# AFE.net
KiCad netlist of a schematic drawn in Altium Designer
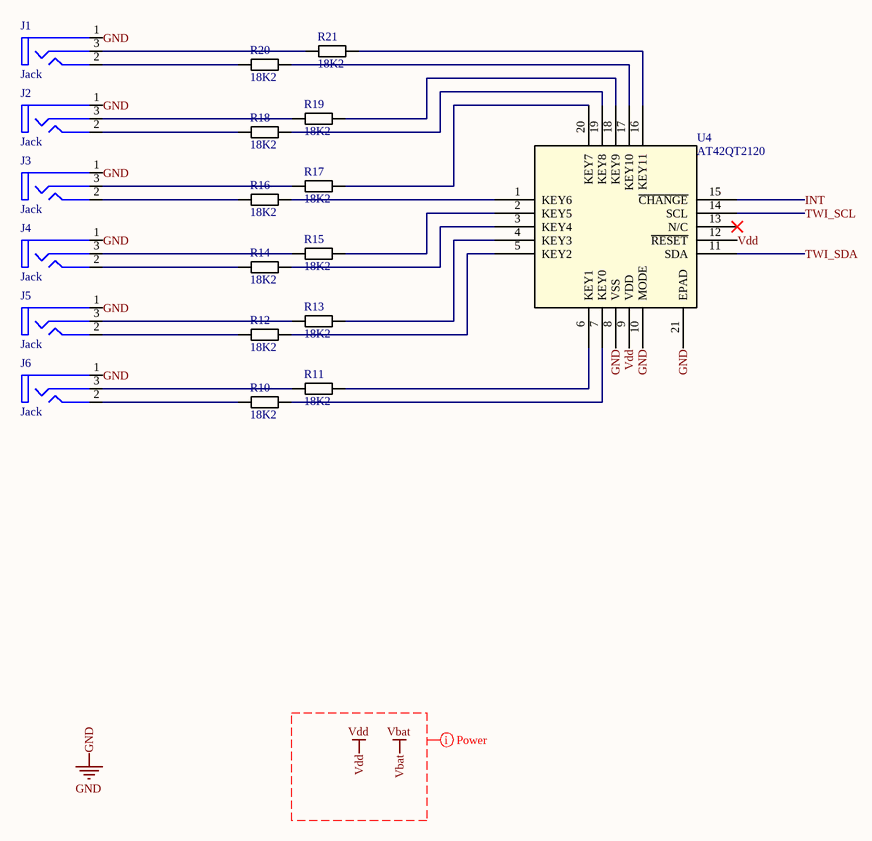
[diagram p0: AFE.SchDoc]

(export (version "E")
  (design (tool "Eeschema 10.0.6"))
  (components
    (comp (ref "J1")
      (value "Jack")
      (footprint "CUI INC SJ2-2510XA")
      (description "CONN JACK STEREO 2.5MM SMD R/A")
      (fields (field (name "PART NUMBER") "SJ2-25103A-SMT-TR") (field (name "MANUFACTURER") "CUI"))
      (libsource (lib "ekuore-library") (part "Jack 3 PIN"))
    )
    (comp (ref "J2")
      (value "Jack")
      (footprint "CUI INC SJ2-2510XA")
      (description "CONN JACK STEREO 2.5MM SMD R/A")
      (fields (field (name "PART NUMBER") "SJ2-25103A-SMT-TR") (field (name "MANUFACTURER") "CUI"))
      (libsource (lib "ekuore-library") (part "Jack 3 PIN"))
    )
    (comp (ref "J3")
      (value "Jack")
      (footprint "CUI INC SJ2-2510XA")
      (description "CONN JACK STEREO 2.5MM SMD R/A")
      (fields (field (name "PART NUMBER") "SJ2-25103A-SMT-TR") (field (name "MANUFACTURER") "CUI"))
      (libsource (lib "ekuore-library") (part "Jack 3 PIN"))
    )
    (comp (ref "J4")
      (value "Jack")
      (footprint "CUI INC SJ2-2510XA")
      (description "CONN JACK STEREO 2.5MM SMD R/A")
      (fields (field (name "PART NUMBER") "SJ2-25103A-SMT-TR") (field (name "MANUFACTURER") "CUI"))
      (libsource (lib "ekuore-library") (part "Jack 3 PIN"))
    )
    (comp (ref "J5")
      (value "Jack")
      (footprint "CUI INC SJ2-2510XA")
      (description "CONN JACK STEREO 2.5MM SMD R/A")
      (fields (field (name "PART NUMBER") "SJ2-25103A-SMT-TR") (field (name "MANUFACTURER") "CUI"))
      (libsource (lib "ekuore-library") (part "Jack 3 PIN"))
    )
    (comp (ref "J6")
      (value "Jack")
      (footprint "CUI INC SJ2-2510XA")
      (description "CONN JACK STEREO 2.5MM SMD R/A")
      (fields (field (name "PART NUMBER") "SJ2-25103A-SMT-TR") (field (name "MANUFACTURER") "CUI"))
      (libsource (lib "ekuore-library") (part "Jack 3 PIN"))
    )
    (comp (ref "R10")
      (value "18K2")
      (footprint "RES 0402/1005")
      (description "RES 0402 18K2 1%  63mW")
      (fields (field (name "PART NUMBER") "RC0402FR-0718K2L") (field (name "MANUFACTURER") "Yageo"))
      (libsource (lib "ekuore-library") (part "Resistor"))
    )
    (comp (ref "R11")
      (value "18K2")
      (footprint "RES 0402/1005")
      (description "RES 0402 18K2 1%  63mW")
      (fields (field (name "PART NUMBER") "RC0402FR-0718K2L") (field (name "MANUFACTURER") "Yageo"))
      (libsource (lib "ekuore-library") (part "Resistor"))
    )
    (comp (ref "R12")
      (value "18K2")
      (footprint "RES 0402/1005")
      (description "RES 0402 18K2 1%  63mW")
      (fields (field (name "PART NUMBER") "RC0402FR-0718K2L") (field (name "MANUFACTURER") "Yageo"))
      (libsource (lib "ekuore-library") (part "Resistor"))
    )
    (comp (ref "R13")
      (value "18K2")
      (footprint "RES 0402/1005")
      (description "RES 0402 18K2 1%  63mW")
      (fields (field (name "PART NUMBER") "RC0402FR-0718K2L") (field (name "MANUFACTURER") "Yageo"))
      (libsource (lib "ekuore-library") (part "Resistor"))
    )
    (comp (ref "R14")
      (value "18K2")
      (footprint "RES 0402/1005")
      (description "RES 0402 18K2 1%  63mW")
      (fields (field (name "PART NUMBER") "RC0402FR-0718K2L") (field (name "MANUFACTURER") "Yageo"))
      (libsource (lib "ekuore-library") (part "Resistor"))
    )
    (comp (ref "R15")
      (value "18K2")
      (footprint "RES 0402/1005")
      (description "RES 0402 18K2 1%  63mW")
      (fields (field (name "PART NUMBER") "RC0402FR-0718K2L") (field (name "MANUFACTURER") "Yageo"))
      (libsource (lib "ekuore-library") (part "Resistor"))
    )
    (comp (ref "R16")
      (value "18K2")
      (footprint "RES 0402/1005")
      (description "RES 0402 18K2 1%  63mW")
      (fields (field (name "PART NUMBER") "RC0402FR-0718K2L") (field (name "MANUFACTURER") "Yageo"))
      (libsource (lib "ekuore-library") (part "Resistor"))
    )
    (comp (ref "R17")
      (value "18K2")
      (footprint "RES 0402/1005")
      (description "RES 0402 18K2 1%  63mW")
      (fields (field (name "PART NUMBER") "RC0402FR-0718K2L") (field (name "MANUFACTURER") "Yageo"))
      (libsource (lib "ekuore-library") (part "Resistor"))
    )
    (comp (ref "R18")
      (value "18K2")
      (footprint "RES 0402/1005")
      (description "RES 0402 18K2 1%  63mW")
      (fields (field (name "PART NUMBER") "RC0402FR-0718K2L") (field (name "MANUFACTURER") "Yageo"))
      (libsource (lib "ekuore-library") (part "Resistor"))
    )
    (comp (ref "R19")
      (value "18K2")
      (footprint "RES 0402/1005")
      (description "RES 0402 18K2 1%  63mW")
      (fields (field (name "PART NUMBER") "RC0402FR-0718K2L") (field (name "MANUFACTURER") "Yageo"))
      (libsource (lib "ekuore-library") (part "Resistor"))
    )
    (comp (ref "R20")
      (value "18K2")
      (footprint "RES 0402/1005")
      (description "RES 0402 18K2 1%  63mW")
      (fields (field (name "PART NUMBER") "RC0402FR-0718K2L") (field (name "MANUFACTURER") "Yageo"))
      (libsource (lib "ekuore-library") (part "Resistor"))
    )
    (comp (ref "R21")
      (value "18K2")
      (footprint "RES 0402/1005")
      (description "RES 0402 18K2 1%  63mW")
      (fields (field (name "PART NUMBER") "RC0402FR-0718K2L") (field (name "MANUFACTURER") "Yageo"))
      (libsource (lib "ekuore-library") (part "Resistor"))
    )
    (comp (ref "U4")
      (value "AT42QT2120")
      (footprint "MICROCHIP VQFN-20")
      (description "IC TOUCH SENSOR 12CH 20VQFN")
      (fields (field (name "PART NUMBER") "AT42QT2120-MMHR") (field (name "MANUFACTURER") "Microchip"))
      (libsource (lib "ekuore-library") (part "AT42QT2120-MMHR"))
    )
  )
  (nets
    (net (code "1") (name "/INT") (class "Default")
      (node (ref "U4") (pin "15") (pinfunction "~{CHANGE}_15") (pintype "passive"))
    )
    (net (code "2") (name "/TWI_SCL") (class "Default")
      (node (ref "U4") (pin "14") (pinfunction "SCL_14") (pintype "passive"))
    )
    (net (code "3") (name "/TWI_SDA") (class "Default")
      (node (ref "U4") (pin "11") (pinfunction "SDA_11") (pintype "passive"))
    )
    (net (code "4") (name "GND") (class "Default")
      (node (ref "J1") (pin "1") (pinfunction "Sleeve_1") (pintype "passive"))
      (node (ref "J2") (pin "1") (pinfunction "Sleeve_1") (pintype "passive"))
      (node (ref "J3") (pin "1") (pinfunction "Sleeve_1") (pintype "passive"))
      (node (ref "J4") (pin "1") (pinfunction "Sleeve_1") (pintype "passive"))
      (node (ref "J5") (pin "1") (pinfunction "Sleeve_1") (pintype "passive"))
      (node (ref "J6") (pin "1") (pinfunction "Sleeve_1") (pintype "passive"))
      (node (ref "U4") (pin "10") (pinfunction "MODE_10") (pintype "passive"))
      (node (ref "U4") (pin "21") (pinfunction "EPAD_21") (pintype "passive"))
      (node (ref "U4") (pin "8") (pinfunction "VSS_8") (pintype "passive"))
    )
    (net (code "5") (name "Net-(J1-Ring)") (class "Default")
      (node (ref "J1") (pin "3") (pinfunction "Ring_3") (pintype "passive"))
      (node (ref "R21") (pin "1") (pinfunction "1_1") (pintype "passive"))
    )
    (net (code "6") (name "Net-(J1-Tip)") (class "Default")
      (node (ref "J1") (pin "2") (pinfunction "Tip_2") (pintype "passive"))
      (node (ref "R20") (pin "1") (pinfunction "1_1") (pintype "passive"))
    )
    (net (code "7") (name "Net-(J2-Ring)") (class "Default")
      (node (ref "J2") (pin "3") (pinfunction "Ring_3") (pintype "passive"))
      (node (ref "R19") (pin "1") (pinfunction "1_1") (pintype "passive"))
    )
    (net (code "8") (name "Net-(J2-Tip)") (class "Default")
      (node (ref "J2") (pin "2") (pinfunction "Tip_2") (pintype "passive"))
      (node (ref "R18") (pin "1") (pinfunction "1_1") (pintype "passive"))
    )
    (net (code "9") (name "Net-(J3-Ring)") (class "Default")
      (node (ref "J3") (pin "3") (pinfunction "Ring_3") (pintype "passive"))
      (node (ref "R17") (pin "1") (pinfunction "1_1") (pintype "passive"))
    )
    (net (code "10") (name "Net-(J3-Tip)") (class "Default")
      (node (ref "J3") (pin "2") (pinfunction "Tip_2") (pintype "passive"))
      (node (ref "R16") (pin "1") (pinfunction "1_1") (pintype "passive"))
    )
    (net (code "11") (name "Net-(J4-Ring)") (class "Default")
      (node (ref "J4") (pin "3") (pinfunction "Ring_3") (pintype "passive"))
      (node (ref "R15") (pin "1") (pinfunction "1_1") (pintype "passive"))
    )
    (net (code "12") (name "Net-(J4-Tip)") (class "Default")
      (node (ref "J4") (pin "2") (pinfunction "Tip_2") (pintype "passive"))
      (node (ref "R14") (pin "1") (pinfunction "1_1") (pintype "passive"))
    )
    (net (code "13") (name "Net-(J5-Ring)") (class "Default")
      (node (ref "J5") (pin "3") (pinfunction "Ring_3") (pintype "passive"))
      (node (ref "R13") (pin "1") (pinfunction "1_1") (pintype "passive"))
    )
    (net (code "14") (name "Net-(J5-Tip)") (class "Default")
      (node (ref "J5") (pin "2") (pinfunction "Tip_2") (pintype "passive"))
      (node (ref "R12") (pin "1") (pinfunction "1_1") (pintype "passive"))
    )
    (net (code "15") (name "Net-(J6-Ring)") (class "Default")
      (node (ref "J6") (pin "3") (pinfunction "Ring_3") (pintype "passive"))
      (node (ref "R11") (pin "1") (pinfunction "1_1") (pintype "passive"))
    )
    (net (code "16") (name "Net-(J6-Tip)") (class "Default")
      (node (ref "J6") (pin "2") (pinfunction "Tip_2") (pintype "passive"))
      (node (ref "R10") (pin "1") (pinfunction "1_1") (pintype "passive"))
    )
    (net (code "17") (name "Net-(U4-KEY0)") (class "Default")
      (node (ref "R10") (pin "2") (pinfunction "2_2") (pintype "passive"))
      (node (ref "U4") (pin "7") (pinfunction "KEY0_7") (pintype "passive"))
    )
    (net (code "18") (name "Net-(U4-KEY1)") (class "Default")
      (node (ref "R11") (pin "2") (pinfunction "2_2") (pintype "passive"))
      (node (ref "U4") (pin "6") (pinfunction "KEY1_6") (pintype "passive"))
    )
    (net (code "19") (name "Net-(U4-KEY2)") (class "Default")
      (node (ref "R12") (pin "2") (pinfunction "2_2") (pintype "passive"))
      (node (ref "U4") (pin "5") (pinfunction "KEY2_5") (pintype "passive"))
    )
    (net (code "20") (name "Net-(U4-KEY3)") (class "Default")
      (node (ref "R13") (pin "2") (pinfunction "2_2") (pintype "passive"))
      (node (ref "U4") (pin "4") (pinfunction "KEY3_4") (pintype "passive"))
    )
    (net (code "21") (name "Net-(U4-KEY4)") (class "Default")
      (node (ref "R14") (pin "2") (pinfunction "2_2") (pintype "passive"))
      (node (ref "U4") (pin "3") (pinfunction "KEY4_3") (pintype "passive"))
    )
    (net (code "22") (name "Net-(U4-KEY5)") (class "Default")
      (node (ref "R15") (pin "2") (pinfunction "2_2") (pintype "passive"))
      (node (ref "U4") (pin "2") (pinfunction "KEY5_2") (pintype "passive"))
    )
    (net (code "23") (name "Net-(U4-KEY6)") (class "Default")
      (node (ref "R16") (pin "2") (pinfunction "2_2") (pintype "passive"))
      (node (ref "U4") (pin "1") (pinfunction "KEY6_1") (pintype "passive"))
    )
    (net (code "24") (name "Net-(U4-KEY7)") (class "Default")
      (node (ref "R17") (pin "2") (pinfunction "2_2") (pintype "passive"))
      (node (ref "U4") (pin "20") (pinfunction "KEY7_20") (pintype "passive"))
    )
    (net (code "25") (name "Net-(U4-KEY8)") (class "Default")
      (node (ref "R18") (pin "2") (pinfunction "2_2") (pintype "passive"))
      (node (ref "U4") (pin "19") (pinfunction "KEY8_19") (pintype "passive"))
    )
    (net (code "26") (name "Net-(U4-KEY9)") (class "Default")
      (node (ref "R19") (pin "2") (pinfunction "2_2") (pintype "passive"))
      (node (ref "U4") (pin "18") (pinfunction "KEY9_18") (pintype "passive"))
    )
    (net (code "27") (name "Net-(U4-KEY10)") (class "Default")
      (node (ref "R20") (pin "2") (pinfunction "2_2") (pintype "passive"))
      (node (ref "U4") (pin "17") (pinfunction "KEY10_17") (pintype "passive"))
    )
    (net (code "28") (name "Net-(U4-KEY11)") (class "Default")
      (node (ref "R21") (pin "2") (pinfunction "2_2") (pintype "passive"))
      (node (ref "U4") (pin "16") (pinfunction "KEY11_16") (pintype "passive"))
    )
    (net (code "30") (name "Vdd") (class "Default")
      (node (ref "U4") (pin "12") (pinfunction "~{RESET}_12") (pintype "passive"))
      (node (ref "U4") (pin "9") (pinfunction "VDD_9") (pintype "passive"))
    )
    (net (code "31") (name "unconnected-(U4-N{slash}C-Pad13)") (class "Default")
      (node (ref "U4") (pin "13") (pinfunction "N/C_13") (pintype "passive+no_connect"))
    )
  )
)
